# shield.net
KiCad netlist of a schematic drawn in EAGLE
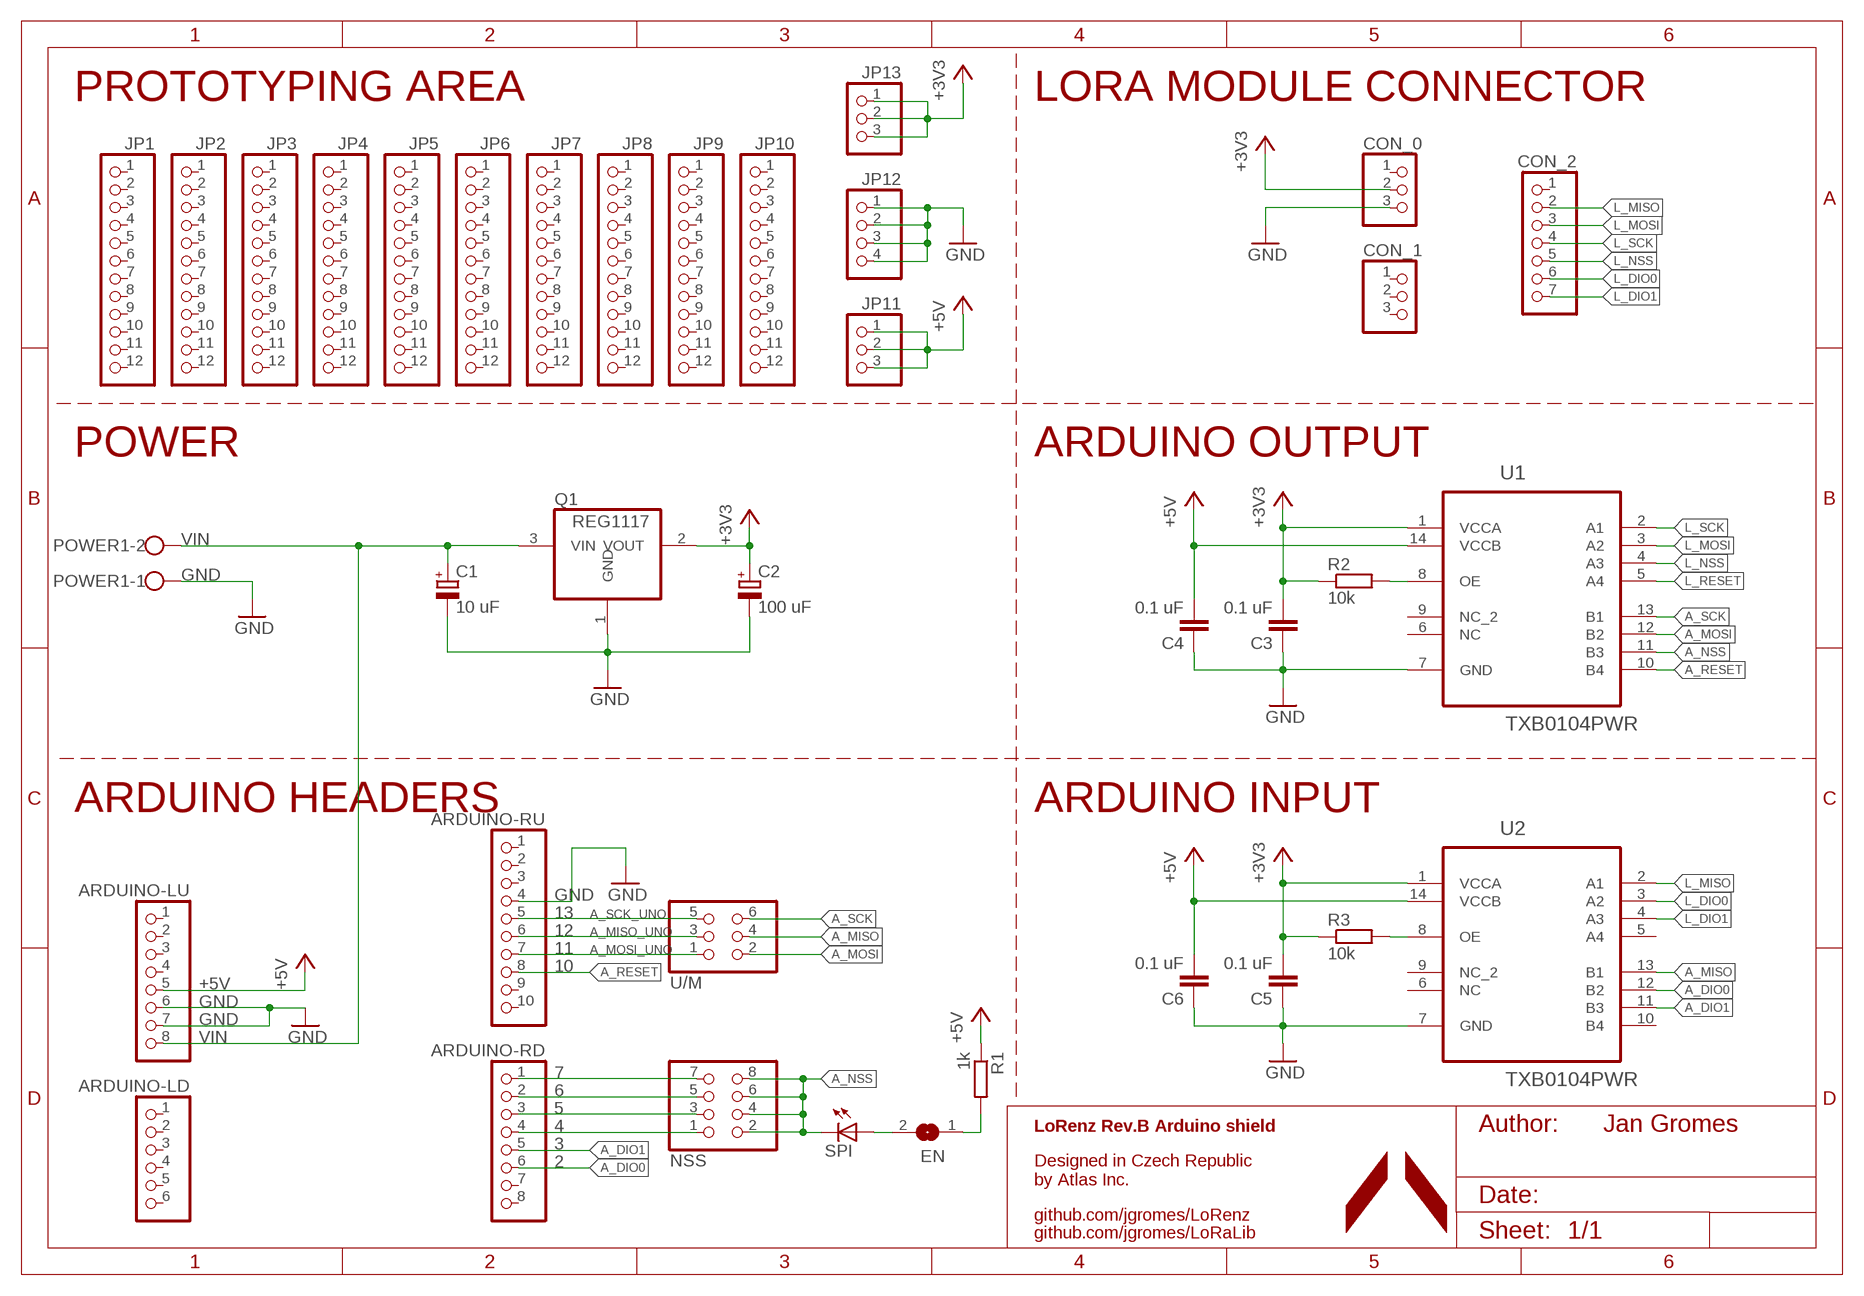
[diagram p0: schematic, sheet 1]

(export (version "E")
  (design (tool "Eeschema 10.0.6"))
  (components
    (comp (ref "ARDUINO-LD")
      (value "PINHD-1X6")
      (footprint "eagle-import:1X06")
      (libsource (lib "eagle-import") (part "PINHD-1X6"))
    )
    (comp (ref "ARDUINO-LU")
      (value "PINHD-1X8")
      (footprint "eagle-import:1X08")
      (libsource (lib "eagle-import") (part "PINHD-1X8"))
    )
    (comp (ref "ARDUINO-RD")
      (value "PINHD-1X8")
      (footprint "eagle-import:1X08")
      (libsource (lib "eagle-import") (part "PINHD-1X8"))
    )
    (comp (ref "ARDUINO-RU")
      (value "PINHD-1X10")
      (footprint "eagle-import:1X10")
      (libsource (lib "eagle-import") (part "PINHD-1X10"))
    )
    (comp (ref "C1")
      (value "10 uF")
      (footprint "eagle-import:SMC_A")
      (libsource (lib "eagle-import") (part "CPOL-EUSMCA"))
    )
    (comp (ref "C2")
      (value "100 uF")
      (footprint "eagle-import:SMC_B")
      (libsource (lib "eagle-import") (part "CPOL-EUSMCB"))
    )
    (comp (ref "C3")
      (value "0.1 uF")
      (footprint "eagle-import:C0603")
      (libsource (lib "eagle-import") (part "C-EUC0603"))
    )
    (comp (ref "C4")
      (value "0.1 uF")
      (footprint "eagle-import:C0603")
      (libsource (lib "eagle-import") (part "C-EUC0603"))
    )
    (comp (ref "C5")
      (value "0.1 uF")
      (footprint "eagle-import:C0603")
      (libsource (lib "eagle-import") (part "C-EUC0603"))
    )
    (comp (ref "C6")
      (value "0.1 uF")
      (footprint "eagle-import:C0603")
      (libsource (lib "eagle-import") (part "C-EUC0603"))
    )
    (comp (ref "CON_0")
      (value "PINHD-1X3")
      (footprint "eagle-import:1X03")
      (libsource (lib "eagle-import") (part "pinhead_PINHD-1X3"))
    )
    (comp (ref "CON_1")
      (value "PINHD-1X3")
      (footprint "eagle-import:1X03")
      (libsource (lib "eagle-import") (part "pinhead_PINHD-1X3"))
    )
    (comp (ref "CON_2")
      (value "PINHD-1X7")
      (footprint "eagle-import:1X07")
      (libsource (lib "eagle-import") (part "PINHD-1X7"))
    )
    (comp (ref "EN") (value "SJ") (footprint "eagle-import:SJ") (libsource (lib "eagle-import") (part "SJ")))
    (comp (ref "JP1")
      (value "PINHD-1X12-CB")
      (footprint "eagle-import:1X12-CB")
      (libsource (lib "eagle-import") (part "PINHD-1X12-CB"))
    )
    (comp (ref "JP2")
      (value "PINHD-1X12-CB")
      (footprint "eagle-import:1X12-CB")
      (libsource (lib "eagle-import") (part "PINHD-1X12-CB"))
    )
    (comp (ref "JP3")
      (value "PINHD-1X12-CB")
      (footprint "eagle-import:1X12-CB")
      (libsource (lib "eagle-import") (part "PINHD-1X12-CB"))
    )
    (comp (ref "JP4")
      (value "PINHD-1X12-CB")
      (footprint "eagle-import:1X12-CB")
      (libsource (lib "eagle-import") (part "PINHD-1X12-CB"))
    )
    (comp (ref "JP5")
      (value "PINHD-1X12-CB")
      (footprint "eagle-import:1X12-CB")
      (libsource (lib "eagle-import") (part "PINHD-1X12-CB"))
    )
    (comp (ref "JP6")
      (value "PINHD-1X12-CB")
      (footprint "eagle-import:1X12-CB")
      (libsource (lib "eagle-import") (part "PINHD-1X12-CB"))
    )
    (comp (ref "JP7")
      (value "PINHD-1X12-CB")
      (footprint "eagle-import:1X12-CB")
      (libsource (lib "eagle-import") (part "PINHD-1X12-CB"))
    )
    (comp (ref "JP8")
      (value "PINHD-1X12-CB")
      (footprint "eagle-import:1X12-CB")
      (libsource (lib "eagle-import") (part "PINHD-1X12-CB"))
    )
    (comp (ref "JP9")
      (value "PINHD-1X12-CB")
      (footprint "eagle-import:1X12-CB")
      (libsource (lib "eagle-import") (part "PINHD-1X12-CB"))
    )
    (comp (ref "JP10")
      (value "PINHD-1X12-CB")
      (footprint "eagle-import:1X12-CB")
      (libsource (lib "eagle-import") (part "PINHD-1X12-CB"))
    )
    (comp (ref "JP11")
      (value "PINHD-1X3CB")
      (footprint "eagle-import:1X03-CLEANBIG")
      (libsource (lib "eagle-import") (part "PINHD-1X3CB"))
    )
    (comp (ref "JP12")
      (value "PINHD-1X4")
      (footprint "eagle-import:1X04-CLEANBIG")
      (libsource (lib "eagle-import") (part "PINHD-1X4"))
    )
    (comp (ref "JP13")
      (value "PINHD-1X3CB")
      (footprint "eagle-import:1X03-CLEANBIG")
      (libsource (lib "eagle-import") (part "PINHD-1X3CB"))
    )
    (comp (ref "NSS")
      (value "PINHD-2X4")
      (footprint "eagle-import:2X04")
      (libsource (lib "eagle-import") (part "PINHD-2X4"))
    )
    (comp (ref "POWER1")
      (value "W237-102")
      (footprint "eagle-import:W237-102")
      (fields (field (name "MPN") "237-102"))
      (libsource (lib "eagle-import") (part "W237-102"))
    )
    (comp (ref "Q1")
      (value "REG1117")
      (footprint "eagle-import:SOT223")
      (libsource (lib "eagle-import") (part "REG1117"))
    )
    (comp (ref "R1")
      (value "1k")
      (footprint "eagle-import:R0603")
      (libsource (lib "eagle-import") (part "R-EU_R0603"))
    )
    (comp (ref "R2")
      (value "10k")
      (footprint "eagle-import:R0603")
      (libsource (lib "eagle-import") (part "R-EU_R0603"))
    )
    (comp (ref "R3")
      (value "10k")
      (footprint "eagle-import:R0603")
      (libsource (lib "eagle-import") (part "R-EU_R0603"))
    )
    (comp (ref "SPI")
      (value "LEDSML0603")
      (footprint "eagle-import:SML0603")
      (libsource (lib "eagle-import") (part "LEDSML0603"))
    )
    (comp (ref "U/M")
      (value "PINHD-2X3")
      (footprint "eagle-import:2X03")
      (libsource (lib "eagle-import") (part "PINHD-2X3"))
    )
    (comp (ref "U1")
      (value "TXB0104PWR")
      (footprint "eagle-import:SOP65P640X120-14N")
      (libsource (lib "eagle-import") (part "TXB0104PWR"))
    )
    (comp (ref "U2")
      (value "TXB0104PWR")
      (footprint "eagle-import:SOP65P640X120-14N")
      (libsource (lib "eagle-import") (part "TXB0104PWR"))
    )
  )
  (nets
    (net (code "1") (name "+3V3") (class "Default")
      (node (ref "C2") (pin "+") (pinfunction "+_+") (pintype "passive"))
      (node (ref "C3") (pin "2") (pinfunction "2_2") (pintype "passive"))
      (node (ref "C5") (pin "2") (pinfunction "2_2") (pintype "passive"))
      (node (ref "CON_0") (pin "2") (pinfunction "2_2") (pintype "passive"))
      (node (ref "JP13") (pin "1") (pinfunction "1_1") (pintype "passive"))
      (node (ref "JP13") (pin "2") (pinfunction "2_2") (pintype "passive"))
      (node (ref "JP13") (pin "3") (pinfunction "3_3") (pintype "passive"))
      (node (ref "Q1") (pin "2") (pinfunction "VOUT_2") (pintype "output"))
      (node (ref "R2") (pin "1") (pinfunction "1_1") (pintype "passive"))
      (node (ref "R3") (pin "1") (pinfunction "1_1") (pintype "passive"))
      (node (ref "U1") (pin "1") (pinfunction "VCCA_1") (pintype "power_in"))
      (node (ref "U2") (pin "1") (pinfunction "VCCA_1") (pintype "power_in"))
    )
    (net (code "2") (name "+5V") (class "Default")
      (node (ref "ARDUINO-LU") (pin "5") (pinfunction "5_5") (pintype "passive"))
      (node (ref "C4") (pin "2") (pinfunction "2_2") (pintype "passive"))
      (node (ref "C6") (pin "2") (pinfunction "2_2") (pintype "passive"))
      (node (ref "JP11") (pin "1") (pinfunction "1_1") (pintype "passive"))
      (node (ref "JP11") (pin "2") (pinfunction "2_2") (pintype "passive"))
      (node (ref "JP11") (pin "3") (pinfunction "3_3") (pintype "passive"))
      (node (ref "R1") (pin "1") (pinfunction "1_1") (pintype "passive"))
      (node (ref "U1") (pin "14") (pinfunction "VCCB_14") (pintype "power_in"))
      (node (ref "U2") (pin "14") (pinfunction "VCCB_14") (pintype "power_in"))
    )
    (net (code "3") (name "/A_MISO_UNO") (class "Default")
      (node (ref "ARDUINO-RU") (pin "6") (pinfunction "6_6") (pintype "passive"))
      (node (ref "U/M") (pin "3") (pinfunction "3_3") (pintype "passive"))
    )
    (net (code "4") (name "/A_MOSI_UNO") (class "Default")
      (node (ref "ARDUINO-RU") (pin "7") (pinfunction "7_7") (pintype "passive"))
      (node (ref "U/M") (pin "1") (pinfunction "1_1") (pintype "passive"))
    )
    (net (code "5") (name "/A_SCK_UNO") (class "Default")
      (node (ref "ARDUINO-RU") (pin "5") (pinfunction "5_5") (pintype "passive"))
      (node (ref "U/M") (pin "5") (pinfunction "5_5") (pintype "passive"))
    )
    (net (code "6") (name "/VIN") (class "Default")
      (node (ref "ARDUINO-LU") (pin "8") (pinfunction "8_8") (pintype "passive"))
      (node (ref "C1") (pin "+") (pinfunction "+_+") (pintype "passive"))
      (node (ref "POWER1") (pin "2") (pinfunction "KL_2") (pintype "passive"))
      (node (ref "Q1") (pin "3") (pinfunction "VIN_3") (pintype "input"))
    )
    (net (code "7") (name "A_DIO0") (class "Default")
      (node (ref "ARDUINO-RD") (pin "6") (pinfunction "6_6") (pintype "passive"))
      (node (ref "U2") (pin "12") (pinfunction "B2_12") (pintype "bidirectional"))
    )
    (net (code "8") (name "A_DIO1") (class "Default")
      (node (ref "ARDUINO-RD") (pin "5") (pinfunction "5_5") (pintype "passive"))
      (node (ref "U2") (pin "11") (pinfunction "B3_11") (pintype "bidirectional"))
    )
    (net (code "9") (name "A_MISO") (class "Default")
      (node (ref "U/M") (pin "4") (pinfunction "4_4") (pintype "passive"))
      (node (ref "U2") (pin "13") (pinfunction "B1_13") (pintype "bidirectional"))
    )
    (net (code "10") (name "A_MOSI") (class "Default")
      (node (ref "U/M") (pin "2") (pinfunction "2_2") (pintype "passive"))
      (node (ref "U1") (pin "12") (pinfunction "B2_12") (pintype "bidirectional"))
    )
    (net (code "11") (name "A_NSS") (class "Default")
      (node (ref "NSS") (pin "2") (pinfunction "2_2") (pintype "passive"))
      (node (ref "NSS") (pin "4") (pinfunction "4_4") (pintype "passive"))
      (node (ref "NSS") (pin "6") (pinfunction "6_6") (pintype "passive"))
      (node (ref "NSS") (pin "8") (pinfunction "8_8") (pintype "passive"))
      (node (ref "SPI") (pin "C") (pinfunction "C_C") (pintype "passive"))
      (node (ref "U1") (pin "11") (pinfunction "B3_11") (pintype "bidirectional"))
    )
    (net (code "12") (name "A_RESET") (class "Default")
      (node (ref "ARDUINO-RU") (pin "8") (pinfunction "8_8") (pintype "passive"))
      (node (ref "U1") (pin "10") (pinfunction "B4_10") (pintype "bidirectional"))
    )
    (net (code "13") (name "A_SCK") (class "Default")
      (node (ref "U/M") (pin "6") (pinfunction "6_6") (pintype "passive"))
      (node (ref "U1") (pin "13") (pinfunction "B1_13") (pintype "bidirectional"))
    )
    (net (code "14") (name "GND") (class "Default")
      (node (ref "ARDUINO-LU") (pin "6") (pinfunction "6_6") (pintype "passive"))
      (node (ref "ARDUINO-LU") (pin "7") (pinfunction "7_7") (pintype "passive"))
      (node (ref "ARDUINO-RU") (pin "4") (pinfunction "4_4") (pintype "passive"))
      (node (ref "C1") (pin "-") (pinfunction "-_-") (pintype "passive"))
      (node (ref "C2") (pin "-") (pinfunction "-_-") (pintype "passive"))
      (node (ref "C3") (pin "1") (pinfunction "1_1") (pintype "passive"))
      (node (ref "C4") (pin "1") (pinfunction "1_1") (pintype "passive"))
      (node (ref "C5") (pin "1") (pinfunction "1_1") (pintype "passive"))
      (node (ref "C6") (pin "1") (pinfunction "1_1") (pintype "passive"))
      (node (ref "CON_0") (pin "3") (pinfunction "3_3") (pintype "passive"))
      (node (ref "JP12") (pin "1") (pinfunction "1_1") (pintype "passive"))
      (node (ref "JP12") (pin "2") (pinfunction "2_2") (pintype "passive"))
      (node (ref "JP12") (pin "3") (pinfunction "3_3") (pintype "passive"))
      (node (ref "JP12") (pin "4") (pinfunction "4_4") (pintype "passive"))
      (node (ref "POWER1") (pin "1") (pinfunction "KL_1") (pintype "passive"))
      (node (ref "Q1") (pin "1") (pinfunction "GND_1") (pintype "power_in"))
      (node (ref "U1") (pin "7") (pinfunction "GND_7") (pintype "passive"))
      (node (ref "U2") (pin "7") (pinfunction "GND_7") (pintype "passive"))
    )
    (net (code "15") (name "L_DIO0") (class "Default")
      (node (ref "CON_2") (pin "6") (pinfunction "6_6") (pintype "passive"))
      (node (ref "U2") (pin "3") (pinfunction "A2_3") (pintype "bidirectional"))
    )
    (net (code "16") (name "L_DIO1") (class "Default")
      (node (ref "CON_2") (pin "7") (pinfunction "7_7") (pintype "passive"))
      (node (ref "U2") (pin "4") (pinfunction "A3_4") (pintype "bidirectional"))
    )
    (net (code "17") (name "L_MISO") (class "Default")
      (node (ref "CON_2") (pin "2") (pinfunction "2_2") (pintype "passive"))
      (node (ref "U2") (pin "2") (pinfunction "A1_2") (pintype "bidirectional"))
    )
    (net (code "18") (name "L_MOSI") (class "Default")
      (node (ref "CON_2") (pin "3") (pinfunction "3_3") (pintype "passive"))
      (node (ref "U1") (pin "3") (pinfunction "A2_3") (pintype "bidirectional"))
    )
    (net (code "19") (name "L_NSS") (class "Default")
      (node (ref "CON_2") (pin "5") (pinfunction "5_5") (pintype "passive"))
      (node (ref "U1") (pin "4") (pinfunction "A3_4") (pintype "bidirectional"))
    )
    (net (code "20") (name "L_RESET") (class "Default")
      (node (ref "U1") (pin "5") (pinfunction "A4_5") (pintype "bidirectional"))
    )
    (net (code "21") (name "L_SCK") (class "Default")
      (node (ref "CON_2") (pin "4") (pinfunction "4_4") (pintype "passive"))
      (node (ref "U1") (pin "2") (pinfunction "A1_2") (pintype "bidirectional"))
    )
    (net (code "22") (name "Net-(ARDUINO-RD-Pad1)") (class "Default")
      (node (ref "ARDUINO-RD") (pin "1") (pinfunction "1_1") (pintype "passive"))
      (node (ref "NSS") (pin "7") (pinfunction "7_7") (pintype "passive"))
    )
    (net (code "23") (name "Net-(ARDUINO-RD-Pad2)") (class "Default")
      (node (ref "ARDUINO-RD") (pin "2") (pinfunction "2_2") (pintype "passive"))
      (node (ref "NSS") (pin "5") (pinfunction "5_5") (pintype "passive"))
    )
    (net (code "24") (name "Net-(ARDUINO-RD-Pad3)") (class "Default")
      (node (ref "ARDUINO-RD") (pin "3") (pinfunction "3_3") (pintype "passive"))
      (node (ref "NSS") (pin "3") (pinfunction "3_3") (pintype "passive"))
    )
    (net (code "25") (name "Net-(ARDUINO-RD-Pad4)") (class "Default")
      (node (ref "ARDUINO-RD") (pin "4") (pinfunction "4_4") (pintype "passive"))
      (node (ref "NSS") (pin "1") (pinfunction "1_1") (pintype "passive"))
    )
    (net (code "26") (name "Net-(EN-Pad1)") (class "Default")
      (node (ref "EN") (pin "1") (pinfunction "1_1") (pintype "passive"))
      (node (ref "R1") (pin "2") (pinfunction "2_2") (pintype "passive"))
    )
    (net (code "27") (name "Net-(EN-Pad2)") (class "Default")
      (node (ref "EN") (pin "2") (pinfunction "2_2") (pintype "passive"))
      (node (ref "SPI") (pin "A") (pinfunction "A_A") (pintype "passive"))
    )
    (net (code "28") (name "Net-(U1-OE)") (class "Default")
      (node (ref "R2") (pin "2") (pinfunction "2_2") (pintype "passive"))
      (node (ref "U1") (pin "8") (pinfunction "OE_8") (pintype "input"))
    )
    (net (code "29") (name "Net-(U2-OE)") (class "Default")
      (node (ref "R3") (pin "2") (pinfunction "2_2") (pintype "passive"))
      (node (ref "U2") (pin "8") (pinfunction "OE_8") (pintype "input"))
    )
    (net (code "30") (name "unconnected-(ARDUINO-LD-Pad1)") (class "Default")
      (node (ref "ARDUINO-LD") (pin "1") (pinfunction "1_1") (pintype "passive"))
    )
    (net (code "31") (name "unconnected-(ARDUINO-LD-Pad2)") (class "Default")
      (node (ref "ARDUINO-LD") (pin "2") (pinfunction "2_2") (pintype "passive"))
    )
    (net (code "32") (name "unconnected-(ARDUINO-LD-Pad3)") (class "Default")
      (node (ref "ARDUINO-LD") (pin "3") (pinfunction "3_3") (pintype "passive"))
    )
    (net (code "33") (name "unconnected-(ARDUINO-LD-Pad4)") (class "Default")
      (node (ref "ARDUINO-LD") (pin "4") (pinfunction "4_4") (pintype "passive"))
    )
    (net (code "34") (name "unconnected-(ARDUINO-LD-Pad5)") (class "Default")
      (node (ref "ARDUINO-LD") (pin "5") (pinfunction "5_5") (pintype "passive"))
    )
    (net (code "35") (name "unconnected-(ARDUINO-LD-Pad6)") (class "Default")
      (node (ref "ARDUINO-LD") (pin "6") (pinfunction "6_6") (pintype "passive"))
    )
    (net (code "36") (name "unconnected-(ARDUINO-LU-Pad1)") (class "Default")
      (node (ref "ARDUINO-LU") (pin "1") (pinfunction "1_1") (pintype "passive"))
    )
    (net (code "37") (name "unconnected-(ARDUINO-LU-Pad2)") (class "Default")
      (node (ref "ARDUINO-LU") (pin "2") (pinfunction "2_2") (pintype "passive"))
    )
    (net (code "38") (name "unconnected-(ARDUINO-LU-Pad3)") (class "Default")
      (node (ref "ARDUINO-LU") (pin "3") (pinfunction "3_3") (pintype "passive"))
    )
    (net (code "39") (name "unconnected-(ARDUINO-LU-Pad4)") (class "Default")
      (node (ref "ARDUINO-LU") (pin "4") (pinfunction "4_4") (pintype "passive"))
    )
    (net (code "40") (name "unconnected-(ARDUINO-RD-Pad7)") (class "Default")
      (node (ref "ARDUINO-RD") (pin "7") (pinfunction "7_7") (pintype "passive"))
    )
    (net (code "41") (name "unconnected-(ARDUINO-RD-Pad8)") (class "Default")
      (node (ref "ARDUINO-RD") (pin "8") (pinfunction "8_8") (pintype "passive"))
    )
    (net (code "42") (name "unconnected-(ARDUINO-RU-Pad1)") (class "Default")
      (node (ref "ARDUINO-RU") (pin "1") (pinfunction "1_1") (pintype "passive"))
    )
    (net (code "43") (name "unconnected-(ARDUINO-RU-Pad2)") (class "Default")
      (node (ref "ARDUINO-RU") (pin "2") (pinfunction "2_2") (pintype "passive"))
    )
    (net (code "44") (name "unconnected-(ARDUINO-RU-Pad3)") (class "Default")
      (node (ref "ARDUINO-RU") (pin "3") (pinfunction "3_3") (pintype "passive"))
    )
    (net (code "45") (name "unconnected-(ARDUINO-RU-Pad9)") (class "Default")
      (node (ref "ARDUINO-RU") (pin "9") (pinfunction "9_9") (pintype "passive"))
    )
    (net (code "46") (name "unconnected-(ARDUINO-RU-Pad10)") (class "Default")
      (node (ref "ARDUINO-RU") (pin "10") (pinfunction "10_10") (pintype "passive"))
    )
    (net (code "47") (name "unconnected-(CON_0-Pad1)") (class "Default")
      (node (ref "CON_0") (pin "1") (pinfunction "1_1") (pintype "passive"))
    )
    (net (code "48") (name "unconnected-(CON_1-Pad1)") (class "Default")
      (node (ref "CON_1") (pin "1") (pinfunction "1_1") (pintype "passive"))
    )
    (net (code "49") (name "unconnected-(CON_1-Pad2)") (class "Default")
      (node (ref "CON_1") (pin "2") (pinfunction "2_2") (pintype "passive"))
    )
    (net (code "50") (name "unconnected-(CON_1-Pad3)") (class "Default")
      (node (ref "CON_1") (pin "3") (pinfunction "3_3") (pintype "passive"))
    )
    (net (code "51") (name "unconnected-(CON_2-Pad1)") (class "Default")
      (node (ref "CON_2") (pin "1") (pinfunction "1_1") (pintype "passive"))
    )
    (net (code "52") (name "unconnected-(JP1-Pad1)") (class "Default")
      (node (ref "JP1") (pin "1") (pinfunction "1_1") (pintype "passive"))
    )
    (net (code "53") (name "unconnected-(JP1-Pad2)") (class "Default")
      (node (ref "JP1") (pin "2") (pinfunction "2_2") (pintype "passive"))
    )
    (net (code "54") (name "unconnected-(JP1-Pad3)") (class "Default")
      (node (ref "JP1") (pin "3") (pinfunction "3_3") (pintype "passive"))
    )
    (net (code "55") (name "unconnected-(JP1-Pad4)") (class "Default")
      (node (ref "JP1") (pin "4") (pinfunction "4_4") (pintype "passive"))
    )
    (net (code "56") (name "unconnected-(JP1-Pad5)") (class "Default")
      (node (ref "JP1") (pin "5") (pinfunction "5_5") (pintype "passive"))
    )
    (net (code "57") (name "unconnected-(JP1-Pad6)") (class "Default")
      (node (ref "JP1") (pin "6") (pinfunction "6_6") (pintype "passive"))
    )
    (net (code "58") (name "unconnected-(JP1-Pad7)") (class "Default")
      (node (ref "JP1") (pin "7") (pinfunction "7_7") (pintype "passive"))
    )
    (net (code "59") (name "unconnected-(JP1-Pad8)") (class "Default")
      (node (ref "JP1") (pin "8") (pinfunction "8_8") (pintype "passive"))
    )
    (net (code "60") (name "unconnected-(JP1-Pad9)") (class "Default")
      (node (ref "JP1") (pin "9") (pinfunction "9_9") (pintype "passive"))
    )
    (net (code "61") (name "unconnected-(JP1-Pad10)") (class "Default")
      (node (ref "JP1") (pin "10") (pinfunction "10_10") (pintype "passive"))
    )
    (net (code "62") (name "unconnected-(JP1-Pad11)") (class "Default")
      (node (ref "JP1") (pin "11") (pinfunction "11_11") (pintype "passive"))
    )
    (net (code "63") (name "unconnected-(JP1-Pad12)") (class "Default")
      (node (ref "JP1") (pin "12") (pinfunction "12_12") (pintype "passive"))
    )
    (net (code "64") (name "unconnected-(JP2-Pad1)") (class "Default")
      (node (ref "JP2") (pin "1") (pinfunction "1_1") (pintype "passive"))
    )
    (net (code "65") (name "unconnected-(JP2-Pad2)") (class "Default")
      (node (ref "JP2") (pin "2") (pinfunction "2_2") (pintype "passive"))
    )
    (net (code "66") (name "unconnected-(JP2-Pad3)") (class "Default")
      (node (ref "JP2") (pin "3") (pinfunction "3_3") (pintype "passive"))
    )
    (net (code "67") (name "unconnected-(JP2-Pad4)") (class "Default")
      (node (ref "JP2") (pin "4") (pinfunction "4_4") (pintype "passive"))
    )
    (net (code "68") (name "unconnected-(JP2-Pad5)") (class "Default")
      (node (ref "JP2") (pin "5") (pinfunction "5_5") (pintype "passive"))
    )
    (net (code "69") (name "unconnected-(JP2-Pad6)") (class "Default")
      (node (ref "JP2") (pin "6") (pinfunction "6_6") (pintype "passive"))
    )
    (net (code "70") (name "unconnected-(JP2-Pad7)") (class "Default")
      (node (ref "JP2") (pin "7") (pinfunction "7_7") (pintype "passive"))
    )
    (net (code "71") (name "unconnected-(JP2-Pad8)") (class "Default")
      (node (ref "JP2") (pin "8") (pinfunction "8_8") (pintype "passive"))
    )
    (net (code "72") (name "unconnected-(JP2-Pad9)") (class "Default")
      (node (ref "JP2") (pin "9") (pinfunction "9_9") (pintype "passive"))
    )
    (net (code "73") (name "unconnected-(JP2-Pad10)") (class "Default")
      (node (ref "JP2") (pin "10") (pinfunction "10_10") (pintype "passive"))
    )
    (net (code "74") (name "unconnected-(JP2-Pad11)") (class "Default")
      (node (ref "JP2") (pin "11") (pinfunction "11_11") (pintype "passive"))
    )
    (net (code "75") (name "unconnected-(JP2-Pad12)") (class "Default")
      (node (ref "JP2") (pin "12") (pinfunction "12_12") (pintype "passive"))
    )
    (net (code "76") (name "unconnected-(JP3-Pad1)") (class "Default")
      (node (ref "JP3") (pin "1") (pinfunction "1_1") (pintype "passive"))
    )
    (net (code "77") (name "unconnected-(JP3-Pad2)") (class "Default")
      (node (ref "JP3") (pin "2") (pinfunction "2_2") (pintype "passive"))
    )
    (net (code "78") (name "unconnected-(JP3-Pad3)") (class "Default")
      (node (ref "JP3") (pin "3") (pinfunction "3_3") (pintype "passive"))
    )
    (net (code "79") (name "unconnected-(JP3-Pad4)") (class "Default")
      (node (ref "JP3") (pin "4") (pinfunction "4_4") (pintype "passive"))
    )
    (net (code "80") (name "unconnected-(JP3-Pad5)") (class "Default")
      (node (ref "JP3") (pin "5") (pinfunction "5_5") (pintype "passive"))
    )
    (net (code "81") (name "unconnected-(JP3-Pad6)") (class "Default")
      (node (ref "JP3") (pin "6") (pinfunction "6_6") (pintype "passive"))
    )
    (net (code "82") (name "unconnected-(JP3-Pad7)") (class "Default")
      (node (ref "JP3") (pin "7") (pinfunction "7_7") (pintype "passive"))
    )
    (net (code "83") (name "unconnected-(JP3-Pad8)") (class "Default")
      (node (ref "JP3") (pin "8") (pinfunction "8_8") (pintype "passive"))
    )
    (net (code "84") (name "unconnected-(JP3-Pad9)") (class "Default")
      (node (ref "JP3") (pin "9") (pinfunction "9_9") (pintype "passive"))
    )
    (net (code "85") (name "unconnected-(JP3-Pad10)") (class "Default")
      (node (ref "JP3") (pin "10") (pinfunction "10_10") (pintype "passive"))
    )
    (net (code "86") (name "unconnected-(JP3-Pad11)") (class "Default")
      (node (ref "JP3") (pin "11") (pinfunction "11_11") (pintype "passive"))
    )
    (net (code "87") (name "unconnected-(JP3-Pad12)") (class "Default")
      (node (ref "JP3") (pin "12") (pinfunction "12_12") (pintype "passive"))
    )
    (net (code "88") (name "unconnected-(JP4-Pad1)") (class "Default")
      (node (ref "JP4") (pin "1") (pinfunction "1_1") (pintype "passive"))
    )
    (net (code "89") (name "unconnected-(JP4-Pad2)") (class "Default")
      (node (ref "JP4") (pin "2") (pinfunction "2_2") (pintype "passive"))
    )
    (net (code "90") (name "unconnected-(JP4-Pad3)") (class "Default")
      (node (ref "JP4") (pin "3") (pinfunction "3_3") (pintype "passive"))
    )
    (net (code "91") (name "unconnected-(JP4-Pad4)") (class "Default")
      (node (ref "JP4") (pin "4") (pinfunction "4_4") (pintype "passive"))
    )
    (net (code "92") (name "unconnected-(JP4-Pad5)") (class "Default")
      (node (ref "JP4") (pin "5") (pinfunction "5_5") (pintype "passive"))
    )
    (net (code "93") (name "unconnected-(JP4-Pad6)") (class "Default")
      (node (ref "JP4") (pin "6") (pinfunction "6_6") (pintype "passive"))
    )
    (net (code "94") (name "unconnected-(JP4-Pad7)") (class "Default")
      (node (ref "JP4") (pin "7") (pinfunction "7_7") (pintype "passive"))
    )
    (net (code "95") (name "unconnected-(JP4-Pad8)") (class "Default")
      (node (ref "JP4") (pin "8") (pinfunction "8_8") (pintype "passive"))
    )
    (net (code "96") (name "unconnected-(JP4-Pad9)") (class "Default")
      (node (ref "JP4") (pin "9") (pinfunction "9_9") (pintype "passive"))
    )
    (net (code "97") (name "unconnected-(JP4-Pad10)") (class "Default")
      (node (ref "JP4") (pin "10") (pinfunction "10_10") (pintype "passive"))
    )
    (net (code "98") (name "unconnected-(JP4-Pad11)") (class "Default")
      (node (ref "JP4") (pin "11") (pinfunction "11_11") (pintype "passive"))
    )
    (net (code "99") (name "unconnected-(JP4-Pad12)") (class "Default")
      (node (ref "JP4") (pin "12") (pinfunction "12_12") (pintype "passive"))
    )
    (net (code "100") (name "unconnected-(JP5-Pad1)") (class "Default")
      (node (ref "JP5") (pin "1") (pinfunction "1_1") (pintype "passive"))
    )
    (net (code "101") (name "unconnected-(JP5-Pad2)") (class "Default")
      (node (ref "JP5") (pin "2") (pinfunction "2_2") (pintype "passive"))
    )
    (net (code "102") (name "unconnected-(JP5-Pad3)") (class "Default")
      (node (ref "JP5") (pin "3") (pinfunction "3_3") (pintype "passive"))
    )
    (net (code "103") (name "unconnected-(JP5-Pad4)") (class "Default")
      (node (ref "JP5") (pin "4") (pinfunction "4_4") (pintype "passive"))
    )
    (net (code "104") (name "unconnected-(JP5-Pad5)") (class "Default")
      (node (ref "JP5") (pin "5") (pinfunction "5_5") (pintype "passive"))
    )
    (net (code "105") (name "unconnected-(JP5-Pad6)") (class "Default")
      (node (ref "JP5") (pin "6") (pinfunction "6_6") (pintype "passive"))
    )
    (net (code "106") (name "unconnected-(JP5-Pad7)") (class "Default")
      (node (ref "JP5") (pin "7") (pinfunction "7_7") (pintype "passive"))
    )
    (net (code "107") (name "unconnected-(JP5-Pad8)") (class "Default")
      (node (ref "JP5") (pin "8") (pinfunction "8_8") (pintype "passive"))
    )
    (net (code "108") (name "unconnected-(JP5-Pad9)") (class "Default")
      (node (ref "JP5") (pin "9") (pinfunction "9_9") (pintype "passive"))
    )
    (net (code "109") (name "unconnected-(JP5-Pad10)") (class "Default")
      (node (ref "JP5") (pin "10") (pinfunction "10_10") (pintype "passive"))
    )
    (net (code "110") (name "unconnected-(JP5-Pad11)") (class "Default")
      (node (ref "JP5") (pin "11") (pinfunction "11_11") (pintype "passive"))
    )
    (net (code "111") (name "unconnected-(JP5-Pad12)") (class "Default")
      (node (ref "JP5") (pin "12") (pinfunction "12_12") (pintype "passive"))
    )
    (net (code "112") (name "unconnected-(JP6-Pad1)") (class "Default")
      (node (ref "JP6") (pin "1") (pinfunction "1_1") (pintype "passive"))
    )
    (net (code "113") (name "unconnected-(JP6-Pad2)") (class "Default")
      (node (ref "JP6") (pin "2") (pinfunction "2_2") (pintype "passive"))
    )
    (net (code "114") (name "unconnected-(JP6-Pad3)") (class "Default")
      (node (ref "JP6") (pin "3") (pinfunction "3_3") (pintype "passive"))
    )
    (net (code "115") (name "unconnected-(JP6-Pad4)") (class "Default")
      (node (ref "JP6") (pin "4") (pinfunction "4_4") (pintype "passive"))
    )
    (net (code "116") (name "unconnected-(JP6-Pad5)") (class "Default")
      (node (ref "JP6") (pin "5") (pinfunction "5_5") (pintype "passive"))
    )
    (net (code "117") (name "unconnected-(JP6-Pad6)") (class "Default")
      (node (ref "JP6") (pin "6") (pinfunction "6_6") (pintype "passive"))
    )
    (net (code "118") (name "unconnected-(JP6-Pad7)") (class "Default")
      (node (ref "JP6") (pin "7") (pinfunction "7_7") (pintype "passive"))
    )
    (net (code "119") (name "unconnected-(JP6-Pad8)") (class "Default")
      (node (ref "JP6") (pin "8") (pinfunction "8_8") (pintype "passive"))
    )
    (net (code "120") (name "unconnected-(JP6-Pad9)") (class "Default")
      (node (ref "JP6") (pin "9") (pinfunction "9_9") (pintype "passive"))
    )
    (net (code "121") (name "unconnected-(JP6-Pad10)") (class "Default")
      (node (ref "JP6") (pin "10") (pinfunction "10_10") (pintype "passive"))
    )
    (net (code "122") (name "unconnected-(JP6-Pad11)") (class "Default")
      (node (ref "JP6") (pin "11") (pinfunction "11_11") (pintype "passive"))
    )
    (net (code "123") (name "unconnected-(JP6-Pad12)") (class "Default")
      (node (ref "JP6") (pin "12") (pinfunction "12_12") (pintype "passive"))
    )
    (net (code "124") (name "unconnected-(JP7-Pad1)") (class "Default")
      (node (ref "JP7") (pin "1") (pinfunction "1_1") (pintype "passive"))
    )
    (net (code "125") (name "unconnected-(JP7-Pad2)") (class "Default")
      (node (ref "JP7") (pin "2") (pinfunction "2_2") (pintype "passive"))
    )
    (net (code "126") (name "unconnected-(JP7-Pad3)") (class "Default")
      (node (ref "JP7") (pin "3") (pinfunction "3_3") (pintype "passive"))
    )
    (net (code "127") (name "unconnected-(JP7-Pad4)") (class "Default")
      (node (ref "JP7") (pin "4") (pinfunction "4_4") (pintype "passive"))
    )
    (net (code "128") (name "unconnected-(JP7-Pad5)") (class "Default")
      (node (ref "JP7") (pin "5") (pinfunction "5_5") (pintype "passive"))
    )
    (net (code "129") (name "unconnected-(JP7-Pad6)") (class "Default")
      (node (ref "JP7") (pin "6") (pinfunction "6_6") (pintype "passive"))
    )
    (net (code "130") (name "unconnected-(JP7-Pad7)") (class "Default")
      (node (ref "JP7") (pin "7") (pinfunction "7_7") (pintype "passive"))
    )
    (net (code "131") (name "unconnected-(JP7-Pad8)") (class "Default")
      (node (ref "JP7") (pin "8") (pinfunction "8_8") (pintype "passive"))
    )
    (net (code "132") (name "unconnected-(JP7-Pad9)") (class "Default")
      (node (ref "JP7") (pin "9") (pinfunction "9_9") (pintype "passive"))
    )
    (net (code "133") (name "unconnected-(JP7-Pad10)") (class "Default")
      (node (ref "JP7") (pin "10") (pinfunction "10_10") (pintype "passive"))
    )
    (net (code "134") (name "unconnected-(JP7-Pad11)") (class "Default")
      (node (ref "JP7") (pin "11") (pinfunction "11_11") (pintype "passive"))
    )
    (net (code "135") (name "unconnected-(JP7-Pad12)") (class "Default")
      (node (ref "JP7") (pin "12") (pinfunction "12_12") (pintype "passive"))
    )
    (net (code "136") (name "unconnected-(JP8-Pad1)") (class "Default")
      (node (ref "JP8") (pin "1") (pinfunction "1_1") (pintype "passive"))
    )
    (net (code "137") (name "unconnected-(JP8-Pad2)") (class "Default")
      (node (ref "JP8") (pin "2") (pinfunction "2_2") (pintype "passive"))
    )
    (net (code "138") (name "unconnected-(JP8-Pad3)") (class "Default")
      (node (ref "JP8") (pin "3") (pinfunction "3_3") (pintype "passive"))
    )
    (net (code "139") (name "unconnected-(JP8-Pad4)") (class "Default")
      (node (ref "JP8") (pin "4") (pinfunction "4_4") (pintype "passive"))
    )
    (net (code "140") (name "unconnected-(JP8-Pad5)") (class "Default")
      (node (ref "JP8") (pin "5") (pinfunction "5_5") (pintype "passive"))
    )
    (net (code "141") (name "unconnected-(JP8-Pad6)") (class "Default")
      (node (ref "JP8") (pin "6") (pinfunction "6_6") (pintype "passive"))
    )
    (net (code "142") (name "unconnected-(JP8-Pad7)") (class "Default")
      (node (ref "JP8") (pin "7") (pinfunction "7_7") (pintype "passive"))
    )
    (net (code "143") (name "unconnected-(JP8-Pad8)") (class "Default")
      (node (ref "JP8") (pin "8") (pinfunction "8_8") (pintype "passive"))
    )
    (net (code "144") (name "unconnected-(JP8-Pad9)") (class "Default")
      (node (ref "JP8") (pin "9") (pinfunction "9_9") (pintype "passive"))
    )
    (net (code "145") (name "unconnected-(JP8-Pad10)") (class "Default")
      (node (ref "JP8") (pin "10") (pinfunction "10_10") (pintype "passive"))
    )
    (net (code "146") (name "unconnected-(JP8-Pad11)") (class "Default")
      (node (ref "JP8") (pin "11") (pinfunction "11_11") (pintype "passive"))
    )
    (net (code "147") (name "unconnected-(JP8-Pad12)") (class "Default")
      (node (ref "JP8") (pin "12") (pinfunction "12_12") (pintype "passive"))
    )
    (net (code "148") (name "unconnected-(JP9-Pad1)") (class "Default")
      (node (ref "JP9") (pin "1") (pinfunction "1_1") (pintype "passive"))
    )
    (net (code "149") (name "unconnected-(JP9-Pad2)") (class "Default")
      (node (ref "JP9") (pin "2") (pinfunction "2_2") (pintype "passive"))
    )
    (net (code "150") (name "unconnected-(JP9-Pad3)") (class "Default")
      (node (ref "JP9") (pin "3") (pinfunction "3_3") (pintype "passive"))
    )
    (net (code "151") (name "unconnected-(JP9-Pad4)") (class "Default")
      (node (ref "JP9") (pin "4") (pinfunction "4_4") (pintype "passive"))
    )
    (net (code "152") (name "unconnected-(JP9-Pad5)") (class "Default")
      (node (ref "JP9") (pin "5") (pinfunction "5_5") (pintype "passive"))
    )
    (net (code "153") (name "unconnected-(JP9-Pad6)") (class "Default")
      (node (ref "JP9") (pin "6") (pinfunction "6_6") (pintype "passive"))
    )
    (net (code "154") (name "unconnected-(JP9-Pad7)") (class "Default")
      (node (ref "JP9") (pin "7") (pinfunction "7_7") (pintype "passive"))
    )
    (net (code "155") (name "unconnected-(JP9-Pad8)") (class "Default")
      (node (ref "JP9") (pin "8") (pinfunction "8_8") (pintype "passive"))
    )
    (net (code "156") (name "unconnected-(JP9-Pad9)") (class "Default")
      (node (ref "JP9") (pin "9") (pinfunction "9_9") (pintype "passive"))
    )
    (net (code "157") (name "unconnected-(JP9-Pad10)") (class "Default")
      (node (ref "JP9") (pin "10") (pinfunction "10_10") (pintype "passive"))
    )
    (net (code "158") (name "unconnected-(JP9-Pad11)") (class "Default")
      (node (ref "JP9") (pin "11") (pinfunction "11_11") (pintype "passive"))
    )
    (net (code "159") (name "unconnected-(JP9-Pad12)") (class "Default")
      (node (ref "JP9") (pin "12") (pinfunction "12_12") (pintype "passive"))
    )
    (net (code "160") (name "unconnected-(JP10-Pad1)") (class "Default")
      (node (ref "JP10") (pin "1") (pinfunction "1_1") (pintype "passive"))
    )
    (net (code "161") (name "unconnected-(JP10-Pad2)") (class "Default")
      (node (ref "JP10") (pin "2") (pinfunction "2_2") (pintype "passive"))
    )
    (net (code "162") (name "unconnected-(JP10-Pad3)") (class "Default")
      (node (ref "JP10") (pin "3") (pinfunction "3_3") (pintype "passive"))
    )
    (net (code "163") (name "unconnected-(JP10-Pad4)") (class "Default")
      (node (ref "JP10") (pin "4") (pinfunction "4_4") (pintype "passive"))
    )
    (net (code "164") (name "unconnected-(JP10-Pad5)") (class "Default")
      (node (ref "JP10") (pin "5") (pinfunction "5_5") (pintype "passive"))
    )
    (net (code "165") (name "unconnected-(JP10-Pad6)") (class "Default")
      (node (ref "JP10") (pin "6") (pinfunction "6_6") (pintype "passive"))
    )
    (net (code "166") (name "unconnected-(JP10-Pad7)") (class "Default")
      (node (ref "JP10") (pin "7") (pinfunction "7_7") (pintype "passive"))
    )
    (net (code "167") (name "unconnected-(JP10-Pad8)") (class "Default")
      (node (ref "JP10") (pin "8") (pinfunction "8_8") (pintype "passive"))
    )
    (net (code "168") (name "unconnected-(JP10-Pad9)") (class "Default")
      (node (ref "JP10") (pin "9") (pinfunction "9_9") (pintype "passive"))
    )
    (net (code "169") (name "unconnected-(JP10-Pad10)") (class "Default")
      (node (ref "JP10") (pin "10") (pinfunction "10_10") (pintype "passive"))
    )
    (net (code "170") (name "unconnected-(JP10-Pad11)") (class "Default")
      (node (ref "JP10") (pin "11") (pinfunction "11_11") (pintype "passive"))
    )
    (net (code "171") (name "unconnected-(JP10-Pad12)") (class "Default")
      (node (ref "JP10") (pin "12") (pinfunction "12_12") (pintype "passive"))
    )
    (net (code "172") (name "unconnected-(U1-NC-Pad6)") (class "Default")
      (node (ref "U1") (pin "6") (pinfunction "NC_6") (pintype "no_connect"))
    )
    (net (code "173") (name "unconnected-(U1-NC_2-Pad9)") (class "Default")
      (node (ref "U1") (pin "9") (pinfunction "NC_2_9") (pintype "no_connect"))
    )
    (net (code "174") (name "unconnected-(U2-A4-Pad5)") (class "Default")
      (node (ref "U2") (pin "5") (pinfunction "A4_5") (pintype "bidirectional"))
    )
    (net (code "175") (name "unconnected-(U2-B4-Pad10)") (class "Default")
      (node (ref "U2") (pin "10") (pinfunction "B4_10") (pintype "bidirectional"))
    )
    (net (code "176") (name "unconnected-(U2-NC-Pad6)") (class "Default")
      (node (ref "U2") (pin "6") (pinfunction "NC_6") (pintype "no_connect"))
    )
    (net (code "177") (name "unconnected-(U2-NC_2-Pad9)") (class "Default")
      (node (ref "U2") (pin "9") (pinfunction "NC_2_9") (pintype "no_connect"))
    )
  )
)
